# STM32F429VET6.net
KiCad netlist of a schematic drawn in Altium Designer
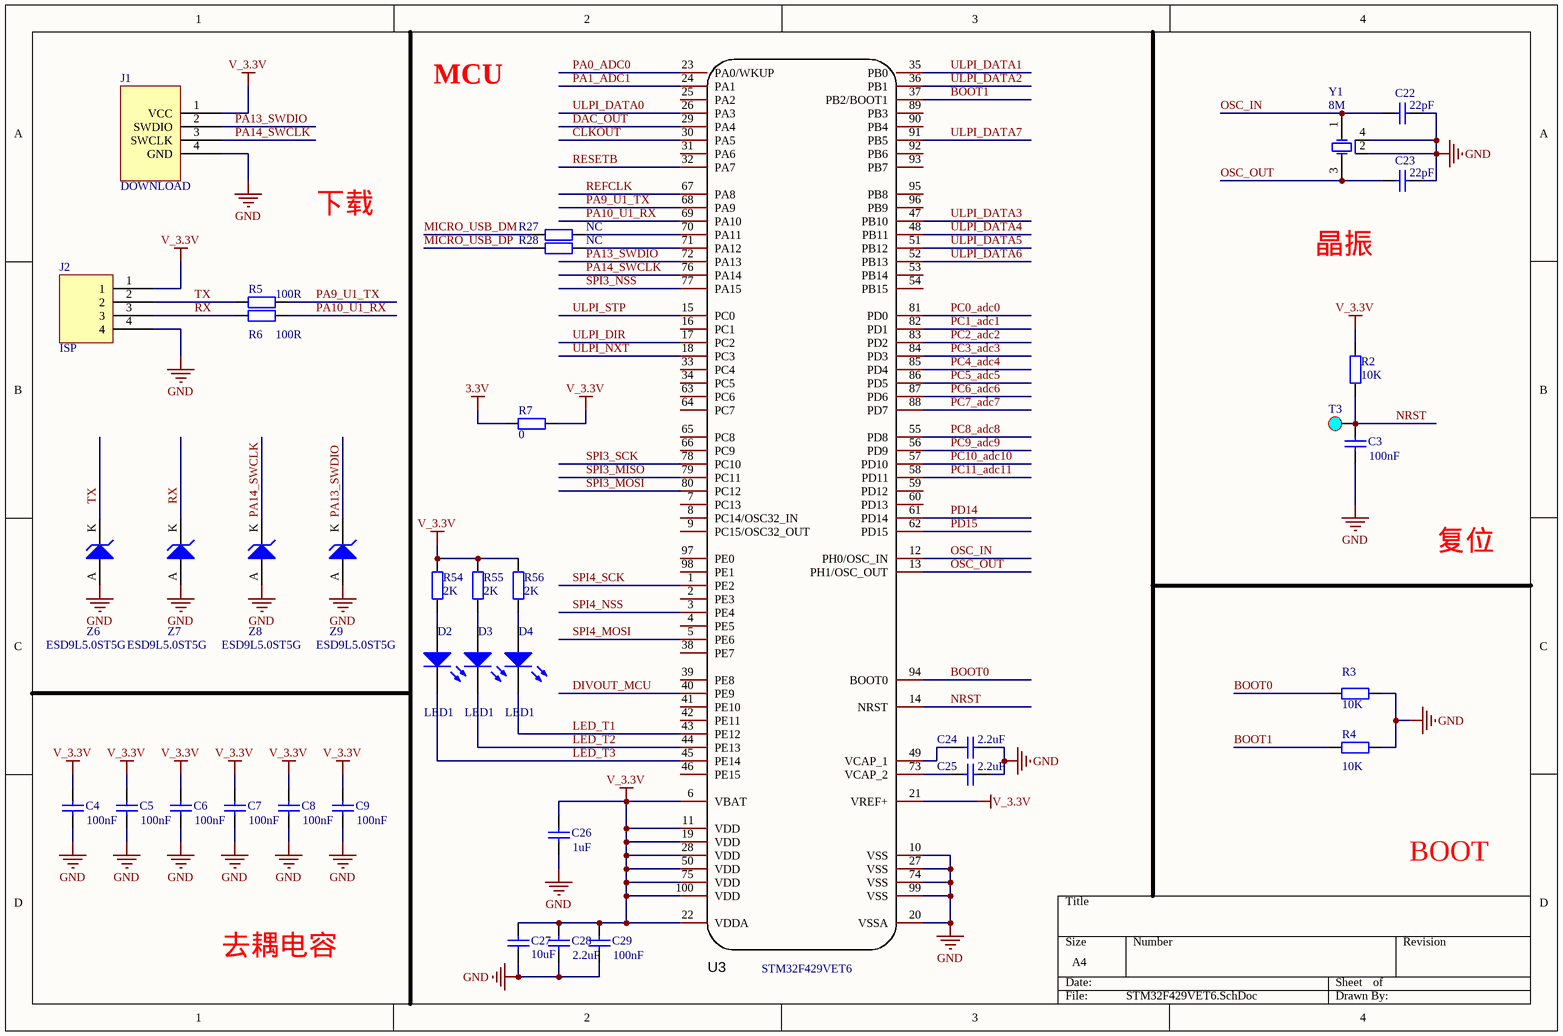
[diagram p0: STM32F429VET6.SchDoc]

(export (version "E")
  (design (tool "Eeschema 10.0.6"))
  (components
    (comp (ref "C3")
      (value "100nF")
      (footprint "C0402")
      (description "Capacitor")
      (fields (field (name "PUBLISHER") "Altium Limited"))
      (libsource (lib "Miscellaneous Devices") (part "Cap"))
    )
    (comp (ref "C4")
      (value "100nF")
      (footprint "C0402")
      (description "Capacitor")
      (fields (field (name "PUBLISHER") "Altium Limited"))
      (libsource (lib "Miscellaneous Devices") (part "Cap"))
    )
    (comp (ref "C5")
      (value "100nF")
      (footprint "C0402")
      (description "Capacitor")
      (fields (field (name "PUBLISHER") "Altium Limited"))
      (libsource (lib "Miscellaneous Devices") (part "Cap"))
    )
    (comp (ref "C6")
      (value "100nF")
      (footprint "C0402")
      (description "Capacitor")
      (fields (field (name "PUBLISHER") "Altium Limited"))
      (libsource (lib "Miscellaneous Devices") (part "Cap"))
    )
    (comp (ref "C7")
      (value "100nF")
      (footprint "C0402")
      (description "Capacitor")
      (fields (field (name "PUBLISHER") "Altium Limited"))
      (libsource (lib "Miscellaneous Devices") (part "Cap"))
    )
    (comp (ref "C8")
      (value "100nF")
      (footprint "C0402")
      (description "Capacitor")
      (fields (field (name "PUBLISHER") "Altium Limited"))
      (libsource (lib "Miscellaneous Devices") (part "Cap"))
    )
    (comp (ref "C9")
      (value "100nF")
      (footprint "C0402")
      (description "Capacitor")
      (fields (field (name "PUBLISHER") "Altium Limited"))
      (libsource (lib "Miscellaneous Devices") (part "Cap"))
    )
    (comp (ref "C22")
      (value "22pF")
      (footprint "C0402")
      (description "Capacitor")
      (fields (field (name "PUBLISHER") "Altium Limited"))
      (libsource (lib "Miscellaneous Devices") (part "Cap"))
    )
    (comp (ref "C23")
      (value "22pF")
      (footprint "C0402")
      (description "Capacitor")
      (fields (field (name "PUBLISHER") "Altium Limited"))
      (libsource (lib "Miscellaneous Devices") (part "Cap"))
    )
    (comp (ref "C24")
      (value "2.2uF")
      (footprint "C0402")
      (description "Capacitor")
      (fields (field (name "PUBLISHER") "Altium Limited"))
      (libsource (lib "Miscellaneous Devices") (part "Cap"))
    )
    (comp (ref "C25")
      (value "2.2uF")
      (footprint "C0402")
      (description "Capacitor")
      (fields (field (name "PUBLISHER") "Altium Limited"))
      (libsource (lib "Miscellaneous Devices") (part "Cap"))
    )
    (comp (ref "C26")
      (value "1uF")
      (footprint "C0402")
      (description "Capacitor")
      (fields (field (name "PUBLISHER") "Altium Limited"))
      (libsource (lib "Miscellaneous Devices") (part "Cap"))
    )
    (comp (ref "C27")
      (value "10uF")
      (footprint "C0603")
      (description "Capacitor")
      (fields (field (name "PUBLISHER") "Altium Limited"))
      (libsource (lib "Miscellaneous Devices") (part "Cap"))
    )
    (comp (ref "C28")
      (value "2.2uF")
      (footprint "C0402")
      (description "Capacitor")
      (fields (field (name "PUBLISHER") "Altium Limited"))
      (libsource (lib "Miscellaneous Devices") (part "Cap"))
    )
    (comp (ref "C29")
      (value "100nF")
      (footprint "C0402")
      (description "Capacitor")
      (fields (field (name "PUBLISHER") "Altium Limited"))
      (libsource (lib "Miscellaneous Devices") (part "Cap"))
    )
    (comp (ref "D2")
      (value "LED1")
      (footprint "LED-0603")
      (description "Typical RED GaAs LED")
      (fields (field (name "PUBLISHER") "Altium Limited"))
      (libsource (lib "Miscellaneous Devices") (part "LED1"))
    )
    (comp (ref "D3")
      (value "LED1")
      (footprint "LED-0603")
      (description "Typical RED GaAs LED")
      (fields (field (name "PUBLISHER") "Altium Limited"))
      (libsource (lib "Miscellaneous Devices") (part "LED1"))
    )
    (comp (ref "D4")
      (value "LED1")
      (footprint "LED-0603")
      (description "Typical RED GaAs LED")
      (fields (field (name "PUBLISHER") "Altium Limited"))
      (libsource (lib "Miscellaneous Devices") (part "LED1"))
    )
    (comp (ref "J1") (value "DOWNLOAD") (footprint "J4") (libsource (lib "Schlib1") (part "下载")))
    (comp (ref "J2") (value "ISP") (footprint "J4") (libsource (lib "Schlib1") (part "J4")))
    (comp (ref "R2")
      (value "10K")
      (footprint "R0402")
      (description "Resistor")
      (fields (field (name "PUBLISHER") "Altium Limited"))
      (libsource (lib "") (part "Res2_1"))
    )
    (comp (ref "R3")
      (value "10K")
      (footprint "R0402")
      (description "Resistor")
      (fields (field (name "PUBLISHER") "Altium Limited"))
      (libsource (lib "") (part "Res2_2"))
    )
    (comp (ref "R4")
      (value "10K")
      (footprint "R0402")
      (description "Resistor")
      (fields (field (name "PUBLISHER") "Altium Limited"))
      (libsource (lib "Miscellaneous Devices") (part "Res2"))
    )
    (comp (ref "R5")
      (value "100R")
      (footprint "R0402")
      (description "Resistor")
      (fields (field (name "PUBLISHER") "Altium Limited"))
      (libsource (lib "Miscellaneous Devices") (part "Res2"))
    )
    (comp (ref "R6")
      (value "100R")
      (footprint "R0402")
      (description "Resistor")
      (fields (field (name "PUBLISHER") "Altium Limited"))
      (libsource (lib "Miscellaneous Devices") (part "Res2"))
    )
    (comp (ref "R7")
      (value "0")
      (footprint "R0402")
      (description "Resistor")
      (fields (field (name "PUBLISHER") "Altium Limited"))
      (libsource (lib "Miscellaneous Devices") (part "Res2"))
    )
    (comp (ref "R27")
      (value "NC")
      (footprint "R0402")
      (description "Resistor")
      (fields (field (name "PUBLISHER") "Altium Limited"))
      (libsource (lib "Miscellaneous Devices") (part "Res2"))
    )
    (comp (ref "R28")
      (value "NC")
      (footprint "R0402")
      (description "Resistor")
      (fields (field (name "PUBLISHER") "Altium Limited"))
      (libsource (lib "Miscellaneous Devices") (part "Res2"))
    )
    (comp (ref "R54")
      (value "2K")
      (footprint "R0402")
      (description "Resistor")
      (fields (field (name "PUBLISHER") "Altium Limited"))
      (libsource (lib "") (part "Res2_1"))
    )
    (comp (ref "R55")
      (value "2K")
      (footprint "R0402")
      (description "Resistor")
      (fields (field (name "PUBLISHER") "Altium Limited"))
      (libsource (lib "") (part "Res2_1"))
    )
    (comp (ref "R56")
      (value "2K")
      (footprint "R0402")
      (description "Resistor")
      (fields (field (name "PUBLISHER") "Altium Limited"))
      (libsource (lib "") (part "Res2_1"))
    )
    (comp (ref "T3")
      (value "~")
      (footprint "TestPoints-0.7")
      (description "TestPoints")
      (libsource (lib "标准原理图库（特种板）") (part "TestPoints"))
    )
    (comp (ref "U3")
      (value "STM32F429VET6")
      (footprint "LQFP-100_L14.0-W14.0-P0.50-LS16.0-BL")
      (fields (field (name "MANUFACTURER") "ST(意法半导体)"))
      (libsource (lib "STM32F429VET6_SRK1201L") (part "STM32F429VET6"))
    )
    (comp (ref "Y1")
      (value "8M")
      (footprint "CRYSTAL_3.2*2.5")
      (libsource (lib "schlib-yves20140829") (part "CRYSTAL-PASSIVE_3225"))
    )
    (comp (ref "Z6")
      (value "ESD9L5.0ST5G")
      (footprint "SOD-923")
      (description "Zener Diode")
      (fields (field (name "PUBLISHER") "Altium Limited"))
      (libsource (lib "Miscellaneous Devices") (part "D Zener"))
    )
    (comp (ref "Z7")
      (value "ESD9L5.0ST5G")
      (footprint "SOD-923")
      (description "Zener Diode")
      (fields (field (name "PUBLISHER") "Altium Limited"))
      (libsource (lib "Miscellaneous Devices") (part "D Zener"))
    )
    (comp (ref "Z8")
      (value "ESD9L5.0ST5G")
      (footprint "SOD-923")
      (description "Zener Diode")
      (fields (field (name "PUBLISHER") "Altium Limited"))
      (libsource (lib "Miscellaneous Devices") (part "D Zener"))
    )
    (comp (ref "Z9")
      (value "ESD9L5.0ST5G")
      (footprint "SOD-923")
      (description "Zener Diode")
      (fields (field (name "PUBLISHER") "Altium Limited"))
      (libsource (lib "Miscellaneous Devices") (part "D Zener"))
    )
  )
  (nets
    (net (code "1") (name "/BOOT0") (class "Default")
      (node (ref "R3") (pin "1") (pinfunction "1_1") (pintype "passive"))
      (node (ref "U3") (pin "94") (pinfunction "BOOT0_94") (pintype "passive"))
    )
    (net (code "2") (name "/BOOT1") (class "Default")
      (node (ref "R4") (pin "2") (pinfunction "2_2") (pintype "passive"))
      (node (ref "U3") (pin "37") (pinfunction "PB2/BOOT1_37") (pintype "passive"))
    )
    (net (code "3") (name "/CLKOUT") (class "Default")
      (node (ref "U3") (pin "30") (pinfunction "PA5_30") (pintype "passive"))
    )
    (net (code "4") (name "/DAC_OUT") (class "Default")
      (node (ref "U3") (pin "29") (pinfunction "PA4_29") (pintype "passive"))
    )
    (net (code "5") (name "/DIVOUT_MCU") (class "Default")
      (node (ref "U3") (pin "40") (pinfunction "PE9_40") (pintype "passive"))
    )
    (net (code "6") (name "/LED_T1") (class "Default")
      (node (ref "D4") (pin "2") (pinfunction "K_2") (pintype "passive"))
      (node (ref "U3") (pin "43") (pinfunction "PE12_43") (pintype "passive"))
    )
    (net (code "7") (name "/LED_T2") (class "Default")
      (node (ref "D3") (pin "2") (pinfunction "K_2") (pintype "passive"))
      (node (ref "U3") (pin "44") (pinfunction "PE13_44") (pintype "passive"))
    )
    (net (code "8") (name "/LED_T3") (class "Default")
      (node (ref "D2") (pin "2") (pinfunction "K_2") (pintype "passive"))
      (node (ref "U3") (pin "45") (pinfunction "PE14_45") (pintype "passive"))
    )
    (net (code "9") (name "/MICRO_USB_DM") (class "Default")
      (node (ref "R27") (pin "2") (pinfunction "2_2") (pintype "passive"))
    )
    (net (code "10") (name "/MICRO_USB_DP") (class "Default")
      (node (ref "R28") (pin "2") (pinfunction "2_2") (pintype "passive"))
    )
    (net (code "11") (name "/NRST") (class "Default")
      (node (ref "C3") (pin "1") (pinfunction "1_1") (pintype "passive"))
      (node (ref "R2") (pin "2") (pinfunction "2_2") (pintype "passive"))
      (node (ref "T3") (pin "1") (pinfunction "1_1") (pintype "passive"))
      (node (ref "U3") (pin "14") (pinfunction "NRST_14") (pintype "passive"))
    )
    (net (code "12") (name "/OSC_IN") (class "Default")
      (node (ref "C22") (pin "1") (pinfunction "1_1") (pintype "passive"))
      (node (ref "U3") (pin "12") (pinfunction "PH0/OSC_IN_12") (pintype "passive"))
      (node (ref "Y1") (pin "1") (pinfunction "INPUT_1") (pintype "passive"))
    )
    (net (code "13") (name "/OSC_OUT") (class "Default")
      (node (ref "C23") (pin "1") (pinfunction "1_1") (pintype "passive"))
      (node (ref "U3") (pin "13") (pinfunction "PH1/OSC_OUT_13") (pintype "passive"))
      (node (ref "Y1") (pin "3") (pinfunction "OUTPUT_3") (pintype "passive"))
    )
    (net (code "14") (name "/PA0_ADC0") (class "Default")
      (node (ref "U3") (pin "23") (pinfunction "PA0/WKUP_23") (pintype "passive"))
    )
    (net (code "15") (name "/PA1_ADC1") (class "Default")
      (node (ref "U3") (pin "24") (pinfunction "PA1_24") (pintype "passive"))
    )
    (net (code "16") (name "/PA9_U1_TX") (class "Default")
      (node (ref "R5") (pin "1") (pinfunction "1_1") (pintype "passive"))
      (node (ref "U3") (pin "68") (pinfunction "PA9_68") (pintype "passive"))
    )
    (net (code "17") (name "/PA10_U1_RX") (class "Default")
      (node (ref "R6") (pin "1") (pinfunction "1_1") (pintype "passive"))
      (node (ref "U3") (pin "69") (pinfunction "PA10_69") (pintype "passive"))
    )
    (net (code "18") (name "/PA13_SWDIO") (class "Default")
      (node (ref "J1") (pin "2") (pinfunction "SWDIO_2") (pintype "passive"))
      (node (ref "U3") (pin "72") (pinfunction "PA13_72") (pintype "passive"))
      (node (ref "Z9") (pin "K") (pinfunction "K_K") (pintype "passive"))
    )
    (net (code "19") (name "/PA14_SWCLK") (class "Default")
      (node (ref "J1") (pin "3") (pinfunction "SWCLK_3") (pintype "passive"))
      (node (ref "U3") (pin "76") (pinfunction "PA14_76") (pintype "passive"))
      (node (ref "Z8") (pin "K") (pinfunction "K_K") (pintype "passive"))
    )
    (net (code "20") (name "/PC0_adc0") (class "Default")
      (node (ref "U3") (pin "81") (pinfunction "PD0_81") (pintype "passive"))
    )
    (net (code "21") (name "/PC1_adc1") (class "Default")
      (node (ref "U3") (pin "82") (pinfunction "PD1_82") (pintype "passive"))
    )
    (net (code "22") (name "/PC2_adc2") (class "Default")
      (node (ref "U3") (pin "83") (pinfunction "PD2_83") (pintype "passive"))
    )
    (net (code "23") (name "/PC3_adc3") (class "Default")
      (node (ref "U3") (pin "84") (pinfunction "PD3_84") (pintype "passive"))
    )
    (net (code "24") (name "/PC4_adc4") (class "Default")
      (node (ref "U3") (pin "85") (pinfunction "PD4_85") (pintype "passive"))
    )
    (net (code "25") (name "/PC5_adc5") (class "Default")
      (node (ref "U3") (pin "86") (pinfunction "PD5_86") (pintype "passive"))
    )
    (net (code "26") (name "/PC6_adc6") (class "Default")
      (node (ref "U3") (pin "87") (pinfunction "PD6_87") (pintype "passive"))
    )
    (net (code "27") (name "/PC7_adc7") (class "Default")
      (node (ref "U3") (pin "88") (pinfunction "PD7_88") (pintype "passive"))
    )
    (net (code "28") (name "/PC8_adc8") (class "Default")
      (node (ref "U3") (pin "55") (pinfunction "PD8_55") (pintype "passive"))
    )
    (net (code "29") (name "/PC9_adc9") (class "Default")
      (node (ref "U3") (pin "56") (pinfunction "PD9_56") (pintype "passive"))
    )
    (net (code "30") (name "/PC10_adc10") (class "Default")
      (node (ref "U3") (pin "57") (pinfunction "PD10_57") (pintype "passive"))
    )
    (net (code "31") (name "/PC11_adc11") (class "Default")
      (node (ref "U3") (pin "58") (pinfunction "PD11_58") (pintype "passive"))
    )
    (net (code "32") (name "/PD14") (class "Default")
      (node (ref "U3") (pin "61") (pinfunction "PD14_61") (pintype "passive"))
    )
    (net (code "33") (name "/PD15") (class "Default")
      (node (ref "U3") (pin "62") (pinfunction "PD15_62") (pintype "passive"))
    )
    (net (code "34") (name "/REFCLK") (class "Default")
      (node (ref "U3") (pin "67") (pinfunction "PA8_67") (pintype "passive"))
    )
    (net (code "35") (name "/RESETB") (class "Default")
      (node (ref "U3") (pin "32") (pinfunction "PA7_32") (pintype "passive"))
    )
    (net (code "36") (name "/RX") (class "Default")
      (node (ref "J2") (pin "3") (pinfunction "3_3") (pintype "passive"))
      (node (ref "R6") (pin "2") (pinfunction "2_2") (pintype "passive"))
      (node (ref "Z7") (pin "K") (pinfunction "K_K") (pintype "passive"))
    )
    (net (code "37") (name "/SPI3_MISO") (class "Default")
      (node (ref "U3") (pin "79") (pinfunction "PC11_79") (pintype "passive"))
    )
    (net (code "38") (name "/SPI3_MOSI") (class "Default")
      (node (ref "U3") (pin "80") (pinfunction "PC12_80") (pintype "passive"))
    )
    (net (code "39") (name "/SPI3_NSS") (class "Default")
      (node (ref "U3") (pin "77") (pinfunction "PA15_77") (pintype "passive"))
    )
    (net (code "40") (name "/SPI3_SCK") (class "Default")
      (node (ref "U3") (pin "78") (pinfunction "PC10_78") (pintype "passive"))
    )
    (net (code "41") (name "/SPI4_MOSI") (class "Default")
      (node (ref "U3") (pin "5") (pinfunction "PE6_5") (pintype "passive"))
    )
    (net (code "42") (name "/SPI4_NSS") (class "Default")
      (node (ref "U3") (pin "3") (pinfunction "PE4_3") (pintype "passive"))
    )
    (net (code "43") (name "/SPI4_SCK") (class "Default")
      (node (ref "U3") (pin "1") (pinfunction "PE2_1") (pintype "passive"))
    )
    (net (code "44") (name "/TX") (class "Default")
      (node (ref "J2") (pin "2") (pinfunction "2_2") (pintype "passive"))
      (node (ref "R5") (pin "2") (pinfunction "2_2") (pintype "passive"))
      (node (ref "Z6") (pin "K") (pinfunction "K_K") (pintype "passive"))
    )
    (net (code "45") (name "/ULPI_DATA0") (class "Default")
      (node (ref "U3") (pin "26") (pinfunction "PA3_26") (pintype "passive"))
    )
    (net (code "46") (name "/ULPI_DATA1") (class "Default")
      (node (ref "U3") (pin "35") (pinfunction "PB0_35") (pintype "passive"))
    )
    (net (code "47") (name "/ULPI_DATA2") (class "Default")
      (node (ref "U3") (pin "36") (pinfunction "PB1_36") (pintype "passive"))
    )
    (net (code "48") (name "/ULPI_DATA3") (class "Default")
      (node (ref "U3") (pin "47") (pinfunction "PB10_47") (pintype "passive"))
    )
    (net (code "49") (name "/ULPI_DATA4") (class "Default")
      (node (ref "U3") (pin "48") (pinfunction "PB11_48") (pintype "passive"))
    )
    (net (code "50") (name "/ULPI_DATA5") (class "Default")
      (node (ref "U3") (pin "51") (pinfunction "PB12_51") (pintype "passive"))
    )
    (net (code "51") (name "/ULPI_DATA6") (class "Default")
      (node (ref "U3") (pin "52") (pinfunction "PB13_52") (pintype "passive"))
    )
    (net (code "52") (name "/ULPI_DATA7") (class "Default")
      (node (ref "U3") (pin "91") (pinfunction "PB5_91") (pintype "passive"))
    )
    (net (code "53") (name "/ULPI_DIR") (class "Default")
      (node (ref "U3") (pin "17") (pinfunction "PC2_17") (pintype "passive"))
    )
    (net (code "54") (name "/ULPI_NXT") (class "Default")
      (node (ref "U3") (pin "18") (pinfunction "PC3_18") (pintype "passive"))
    )
    (net (code "55") (name "/ULPI_STP") (class "Default")
      (node (ref "U3") (pin "15") (pinfunction "PC0_15") (pintype "passive"))
    )
    (net (code "56") (name "3.3V") (class "Default")
      (node (ref "R7") (pin "2") (pinfunction "2_2") (pintype "passive"))
    )
    (net (code "57") (name "GND") (class "Default")
      (node (ref "C22") (pin "2") (pinfunction "2_2") (pintype "passive"))
      (node (ref "C23") (pin "2") (pinfunction "2_2") (pintype "passive"))
      (node (ref "C24") (pin "2") (pinfunction "2_2") (pintype "passive"))
      (node (ref "C25") (pin "2") (pinfunction "2_2") (pintype "passive"))
      (node (ref "C26") (pin "2") (pinfunction "2_2") (pintype "passive"))
      (node (ref "C27") (pin "2") (pinfunction "2_2") (pintype "passive"))
      (node (ref "C28") (pin "2") (pinfunction "2_2") (pintype "passive"))
      (node (ref "C29") (pin "2") (pinfunction "2_2") (pintype "passive"))
      (node (ref "C3") (pin "2") (pinfunction "2_2") (pintype "passive"))
      (node (ref "C4") (pin "2") (pinfunction "2_2") (pintype "passive"))
      (node (ref "C5") (pin "2") (pinfunction "2_2") (pintype "passive"))
      (node (ref "C6") (pin "2") (pinfunction "2_2") (pintype "passive"))
      (node (ref "C7") (pin "2") (pinfunction "2_2") (pintype "passive"))
      (node (ref "C8") (pin "2") (pinfunction "2_2") (pintype "passive"))
      (node (ref "C9") (pin "2") (pinfunction "2_2") (pintype "passive"))
      (node (ref "J1") (pin "4") (pinfunction "GND_4") (pintype "passive"))
      (node (ref "J2") (pin "4") (pinfunction "4_4") (pintype "passive"))
      (node (ref "R3") (pin "2") (pinfunction "2_2") (pintype "passive"))
      (node (ref "R4") (pin "1") (pinfunction "1_1") (pintype "passive"))
      (node (ref "U3") (pin "10") (pinfunction "VSS_10") (pintype "passive"))
      (node (ref "U3") (pin "20") (pinfunction "VSSA_20") (pintype "passive"))
      (node (ref "U3") (pin "27") (pinfunction "VSS_27") (pintype "passive"))
      (node (ref "U3") (pin "74") (pinfunction "VSS_74") (pintype "passive"))
      (node (ref "U3") (pin "99") (pinfunction "VSS_99") (pintype "passive"))
      (node (ref "Y1") (pin "2") (pinfunction "GROUND_2") (pintype "passive"))
      (node (ref "Y1") (pin "4") (pinfunction "GROUND_4") (pintype "passive"))
      (node (ref "Z6") (pin "A") (pinfunction "A_A") (pintype "passive"))
      (node (ref "Z7") (pin "A") (pinfunction "A_A") (pintype "passive"))
      (node (ref "Z8") (pin "A") (pinfunction "A_A") (pintype "passive"))
      (node (ref "Z9") (pin "A") (pinfunction "A_A") (pintype "passive"))
    )
    (net (code "58") (name "Net-(D2-A)") (class "Default")
      (node (ref "D2") (pin "1") (pinfunction "A_1") (pintype "passive"))
      (node (ref "R54") (pin "2") (pinfunction "2_2") (pintype "passive"))
    )
    (net (code "59") (name "Net-(D3-A)") (class "Default")
      (node (ref "D3") (pin "1") (pinfunction "A_1") (pintype "passive"))
      (node (ref "R55") (pin "2") (pinfunction "2_2") (pintype "passive"))
    )
    (net (code "60") (name "Net-(D4-A)") (class "Default")
      (node (ref "D4") (pin "1") (pinfunction "A_1") (pintype "passive"))
      (node (ref "R56") (pin "2") (pinfunction "2_2") (pintype "passive"))
    )
    (net (code "61") (name "Net-(U3-PA11)") (class "Default")
      (node (ref "R27") (pin "1") (pinfunction "1_1") (pintype "passive"))
      (node (ref "U3") (pin "70") (pinfunction "PA11_70") (pintype "passive"))
    )
    (net (code "62") (name "Net-(U3-PA12)") (class "Default")
      (node (ref "R28") (pin "1") (pinfunction "1_1") (pintype "passive"))
      (node (ref "U3") (pin "71") (pinfunction "PA12_71") (pintype "passive"))
    )
    (net (code "63") (name "Net-(U3-VCAP_1)") (class "Default")
      (node (ref "C24") (pin "1") (pinfunction "1_1") (pintype "passive"))
      (node (ref "U3") (pin "49") (pinfunction "VCAP_1_49") (pintype "passive"))
    )
    (net (code "64") (name "Net-(U3-VCAP_2)") (class "Default")
      (node (ref "C25") (pin "1") (pinfunction "1_1") (pintype "passive"))
      (node (ref "U3") (pin "73") (pinfunction "VCAP_2_73") (pintype "passive"))
    )
    (net (code "65") (name "V_3.3V") (class "Default")
      (node (ref "C26") (pin "1") (pinfunction "1_1") (pintype "passive"))
      (node (ref "C27") (pin "1") (pinfunction "1_1") (pintype "passive"))
      (node (ref "C28") (pin "1") (pinfunction "1_1") (pintype "passive"))
      (node (ref "C29") (pin "1") (pinfunction "1_1") (pintype "passive"))
      (node (ref "C4") (pin "1") (pinfunction "1_1") (pintype "passive"))
      (node (ref "C5") (pin "1") (pinfunction "1_1") (pintype "passive"))
      (node (ref "C6") (pin "1") (pinfunction "1_1") (pintype "passive"))
      (node (ref "C7") (pin "1") (pinfunction "1_1") (pintype "passive"))
      (node (ref "C8") (pin "1") (pinfunction "1_1") (pintype "passive"))
      (node (ref "C9") (pin "1") (pinfunction "1_1") (pintype "passive"))
      (node (ref "J1") (pin "1") (pinfunction "VCC_1") (pintype "passive"))
      (node (ref "J2") (pin "1") (pinfunction "1_1") (pintype "passive"))
      (node (ref "R2") (pin "1") (pinfunction "1_1") (pintype "passive"))
      (node (ref "R54") (pin "1") (pinfunction "1_1") (pintype "passive"))
      (node (ref "R55") (pin "1") (pinfunction "1_1") (pintype "passive"))
      (node (ref "R56") (pin "1") (pinfunction "1_1") (pintype "passive"))
      (node (ref "R7") (pin "1") (pinfunction "1_1") (pintype "passive"))
      (node (ref "U3") (pin "100") (pinfunction "VDD_100") (pintype "passive"))
      (node (ref "U3") (pin "11") (pinfunction "VDD_11") (pintype "passive"))
      (node (ref "U3") (pin "19") (pinfunction "VDD_19") (pintype "passive"))
      (node (ref "U3") (pin "21") (pinfunction "VREF+_21") (pintype "passive"))
      (node (ref "U3") (pin "22") (pinfunction "VDDA_22") (pintype "passive"))
      (node (ref "U3") (pin "28") (pinfunction "VDD_28") (pintype "passive"))
      (node (ref "U3") (pin "50") (pinfunction "VDD_50") (pintype "passive"))
      (node (ref "U3") (pin "6") (pinfunction "VBAT_6") (pintype "passive"))
      (node (ref "U3") (pin "75") (pinfunction "VDD_75") (pintype "passive"))
    )
    (net (code "66") (name "unconnected-(U3-PA2-Pad25)") (class "Default")
      (node (ref "U3") (pin "25") (pinfunction "PA2_25") (pintype "passive"))
    )
    (net (code "67") (name "unconnected-(U3-PA6-Pad31)") (class "Default")
      (node (ref "U3") (pin "31") (pinfunction "PA6_31") (pintype "passive"))
    )
    (net (code "68") (name "unconnected-(U3-PB3-Pad89)") (class "Default")
      (node (ref "U3") (pin "89") (pinfunction "PB3_89") (pintype "passive"))
    )
    (net (code "69") (name "unconnected-(U3-PB4-Pad90)") (class "Default")
      (node (ref "U3") (pin "90") (pinfunction "PB4_90") (pintype "passive"))
    )
    (net (code "70") (name "unconnected-(U3-PB6-Pad92)") (class "Default")
      (node (ref "U3") (pin "92") (pinfunction "PB6_92") (pintype "passive"))
    )
    (net (code "71") (name "unconnected-(U3-PB7-Pad93)") (class "Default")
      (node (ref "U3") (pin "93") (pinfunction "PB7_93") (pintype "passive"))
    )
    (net (code "72") (name "unconnected-(U3-PB8-Pad95)") (class "Default")
      (node (ref "U3") (pin "95") (pinfunction "PB8_95") (pintype "passive"))
    )
    (net (code "73") (name "unconnected-(U3-PB9-Pad96)") (class "Default")
      (node (ref "U3") (pin "96") (pinfunction "PB9_96") (pintype "passive"))
    )
    (net (code "74") (name "unconnected-(U3-PB14-Pad53)") (class "Default")
      (node (ref "U3") (pin "53") (pinfunction "PB14_53") (pintype "passive"))
    )
    (net (code "75") (name "unconnected-(U3-PB15-Pad54)") (class "Default")
      (node (ref "U3") (pin "54") (pinfunction "PB15_54") (pintype "passive"))
    )
    (net (code "76") (name "unconnected-(U3-PC1-Pad16)") (class "Default")
      (node (ref "U3") (pin "16") (pinfunction "PC1_16") (pintype "passive"))
    )
    (net (code "77") (name "unconnected-(U3-PC4-Pad33)") (class "Default")
      (node (ref "U3") (pin "33") (pinfunction "PC4_33") (pintype "passive"))
    )
    (net (code "78") (name "unconnected-(U3-PC5-Pad34)") (class "Default")
      (node (ref "U3") (pin "34") (pinfunction "PC5_34") (pintype "passive"))
    )
    (net (code "79") (name "unconnected-(U3-PC6-Pad63)") (class "Default")
      (node (ref "U3") (pin "63") (pinfunction "PC6_63") (pintype "passive"))
    )
    (net (code "80") (name "unconnected-(U3-PC7-Pad64)") (class "Default")
      (node (ref "U3") (pin "64") (pinfunction "PC7_64") (pintype "passive"))
    )
    (net (code "81") (name "unconnected-(U3-PC8-Pad65)") (class "Default")
      (node (ref "U3") (pin "65") (pinfunction "PC8_65") (pintype "passive"))
    )
    (net (code "82") (name "unconnected-(U3-PC9-Pad66)") (class "Default")
      (node (ref "U3") (pin "66") (pinfunction "PC9_66") (pintype "passive"))
    )
    (net (code "83") (name "unconnected-(U3-PC13-Pad7)") (class "Default")
      (node (ref "U3") (pin "7") (pinfunction "PC13_7") (pintype "passive"))
    )
    (net (code "84") (name "unconnected-(U3-PC14{slash}OSC32_IN-Pad8)") (class "Default")
      (node (ref "U3") (pin "8") (pinfunction "PC14/OSC32_IN_8") (pintype "passive"))
    )
    (net (code "85") (name "unconnected-(U3-PC15{slash}OSC32_OUT-Pad9)") (class "Default")
      (node (ref "U3") (pin "9") (pinfunction "PC15/OSC32_OUT_9") (pintype "passive"))
    )
    (net (code "86") (name "unconnected-(U3-PD12-Pad59)") (class "Default")
      (node (ref "U3") (pin "59") (pinfunction "PD12_59") (pintype "passive"))
    )
    (net (code "87") (name "unconnected-(U3-PD13-Pad60)") (class "Default")
      (node (ref "U3") (pin "60") (pinfunction "PD13_60") (pintype "passive"))
    )
    (net (code "88") (name "unconnected-(U3-PE0-Pad97)") (class "Default")
      (node (ref "U3") (pin "97") (pinfunction "PE0_97") (pintype "passive"))
    )
    (net (code "89") (name "unconnected-(U3-PE1-Pad98)") (class "Default")
      (node (ref "U3") (pin "98") (pinfunction "PE1_98") (pintype "passive"))
    )
    (net (code "90") (name "unconnected-(U3-PE3-Pad2)") (class "Default")
      (node (ref "U3") (pin "2") (pinfunction "PE3_2") (pintype "passive"))
    )
    (net (code "91") (name "unconnected-(U3-PE5-Pad4)") (class "Default")
      (node (ref "U3") (pin "4") (pinfunction "PE5_4") (pintype "passive"))
    )
    (net (code "92") (name "unconnected-(U3-PE7-Pad38)") (class "Default")
      (node (ref "U3") (pin "38") (pinfunction "PE7_38") (pintype "passive"))
    )
    (net (code "93") (name "unconnected-(U3-PE8-Pad39)") (class "Default")
      (node (ref "U3") (pin "39") (pinfunction "PE8_39") (pintype "passive"))
    )
    (net (code "94") (name "unconnected-(U3-PE10-Pad41)") (class "Default")
      (node (ref "U3") (pin "41") (pinfunction "PE10_41") (pintype "passive"))
    )
    (net (code "95") (name "unconnected-(U3-PE11-Pad42)") (class "Default")
      (node (ref "U3") (pin "42") (pinfunction "PE11_42") (pintype "passive"))
    )
    (net (code "96") (name "unconnected-(U3-PE15-Pad46)") (class "Default")
      (node (ref "U3") (pin "46") (pinfunction "PE15_46") (pintype "passive"))
    )
  )
)
